# light_board.net
KiCad netlist of a schematic drawn in EAGLE
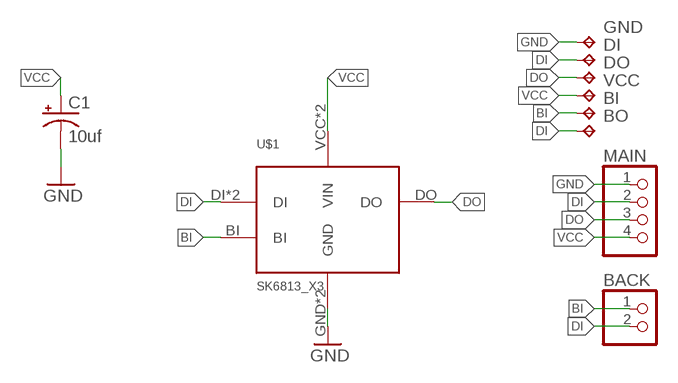
[diagram p0: schematic, sheet 1]

(export (version "E")
  (design (tool "Eeschema 10.0.6"))
  (components
    (comp (ref "BACK")
      (value "PINHD-1X2")
      (footprint "eagle-import:1X02")
      (libsource (lib "eagle-import") (part "PINHD-1X2"))
    )
    (comp (ref "BI")
      (value "TPB1,27")
      (footprint "eagle-import:B1,27")
      (libsource (lib "eagle-import") (part "TPB1,27"))
    )
    (comp (ref "BO")
      (value "TPB1,27")
      (footprint "eagle-import:B1,27")
      (libsource (lib "eagle-import") (part "TPB1,27"))
    )
    (comp (ref "C1")
      (value "10uf")
      (footprint "eagle-import:153CLV-0405")
      (libsource (lib "eagle-import") (part "CPOL-US153CLV-0405"))
    )
    (comp (ref "DI")
      (value "TPB1,27")
      (footprint "eagle-import:B1,27")
      (libsource (lib "eagle-import") (part "TPB1,27"))
    )
    (comp (ref "DO")
      (value "TPB1,27")
      (footprint "eagle-import:B1,27")
      (libsource (lib "eagle-import") (part "TPB1,27"))
    )
    (comp (ref "GND")
      (value "TPB1,27")
      (footprint "eagle-import:B1,27")
      (libsource (lib "eagle-import") (part "TPB1,27"))
    )
    (comp (ref "MAIN")
      (value "PINHD-1X4")
      (footprint "eagle-import:1X04")
      (libsource (lib "eagle-import") (part "PINHD-1X4"))
    )
    (comp (ref "U$1")
      (value "SK6813_X3")
      (footprint "eagle-import:SK6813_X3")
      (libsource (lib "eagle-import") (part "SK6813_X3"))
    )
    (comp (ref "VCC")
      (value "TPB1,27")
      (footprint "eagle-import:B1,27")
      (libsource (lib "eagle-import") (part "TPB1,27"))
    )
  )
  (nets
    (net (code "1") (name "BI") (class "Default")
      (node (ref "BACK") (pin "1") (pinfunction "1_1") (pintype "passive"))
      (node (ref "BI") (pin "TP") (pinfunction "TP_TP") (pintype "input"))
      (node (ref "U$1") (pin "BI") (pinfunction "BI_BI") (pintype "bidirectional"))
    )
    (net (code "2") (name "DI") (class "Default")
      (node (ref "BACK") (pin "2") (pinfunction "2_2") (pintype "passive"))
      (node (ref "BO") (pin "TP") (pinfunction "TP_TP") (pintype "input"))
      (node (ref "DI") (pin "TP") (pinfunction "TP_TP") (pintype "input"))
      (node (ref "MAIN") (pin "2") (pinfunction "2_2") (pintype "passive"))
      (node (ref "U$1") (pin "DI") (pinfunction "DI_DI") (pintype "bidirectional"))
      (node (ref "U$1") (pin "DI@1") (pinfunction "DI_DI@1") (pintype "bidirectional"))
    )
    (net (code "3") (name "DO") (class "Default")
      (node (ref "DO") (pin "TP") (pinfunction "TP_TP") (pintype "input"))
      (node (ref "MAIN") (pin "3") (pinfunction "3_3") (pintype "passive"))
      (node (ref "U$1") (pin "DO") (pinfunction "DO_DO") (pintype "bidirectional"))
    )
    (net (code "4") (name "GND") (class "Default")
      (node (ref "C1") (pin "-") (pinfunction "-_-") (pintype "passive"))
      (node (ref "GND") (pin "TP") (pinfunction "TP_TP") (pintype "input"))
      (node (ref "MAIN") (pin "1") (pinfunction "1_1") (pintype "passive"))
      (node (ref "U$1") (pin "GND") (pinfunction "GND_GND") (pintype "power_in"))
      (node (ref "U$1") (pin "GND@1") (pinfunction "GND_GND@1") (pintype "power_in"))
    )
    (net (code "5") (name "VCC") (class "Default")
      (node (ref "C1") (pin "+") (pinfunction "+_+") (pintype "passive"))
      (node (ref "MAIN") (pin "4") (pinfunction "4_4") (pintype "passive"))
      (node (ref "U$1") (pin "VCC") (pinfunction "VIN_VCC") (pintype "power_in"))
      (node (ref "U$1") (pin "VCC@1") (pinfunction "VIN_VCC@1") (pintype "power_in"))
      (node (ref "VCC") (pin "TP") (pinfunction "TP_TP") (pintype "input"))
    )
  )
)
